# Main.net
KiCad netlist of a schematic drawn in Altium Designer
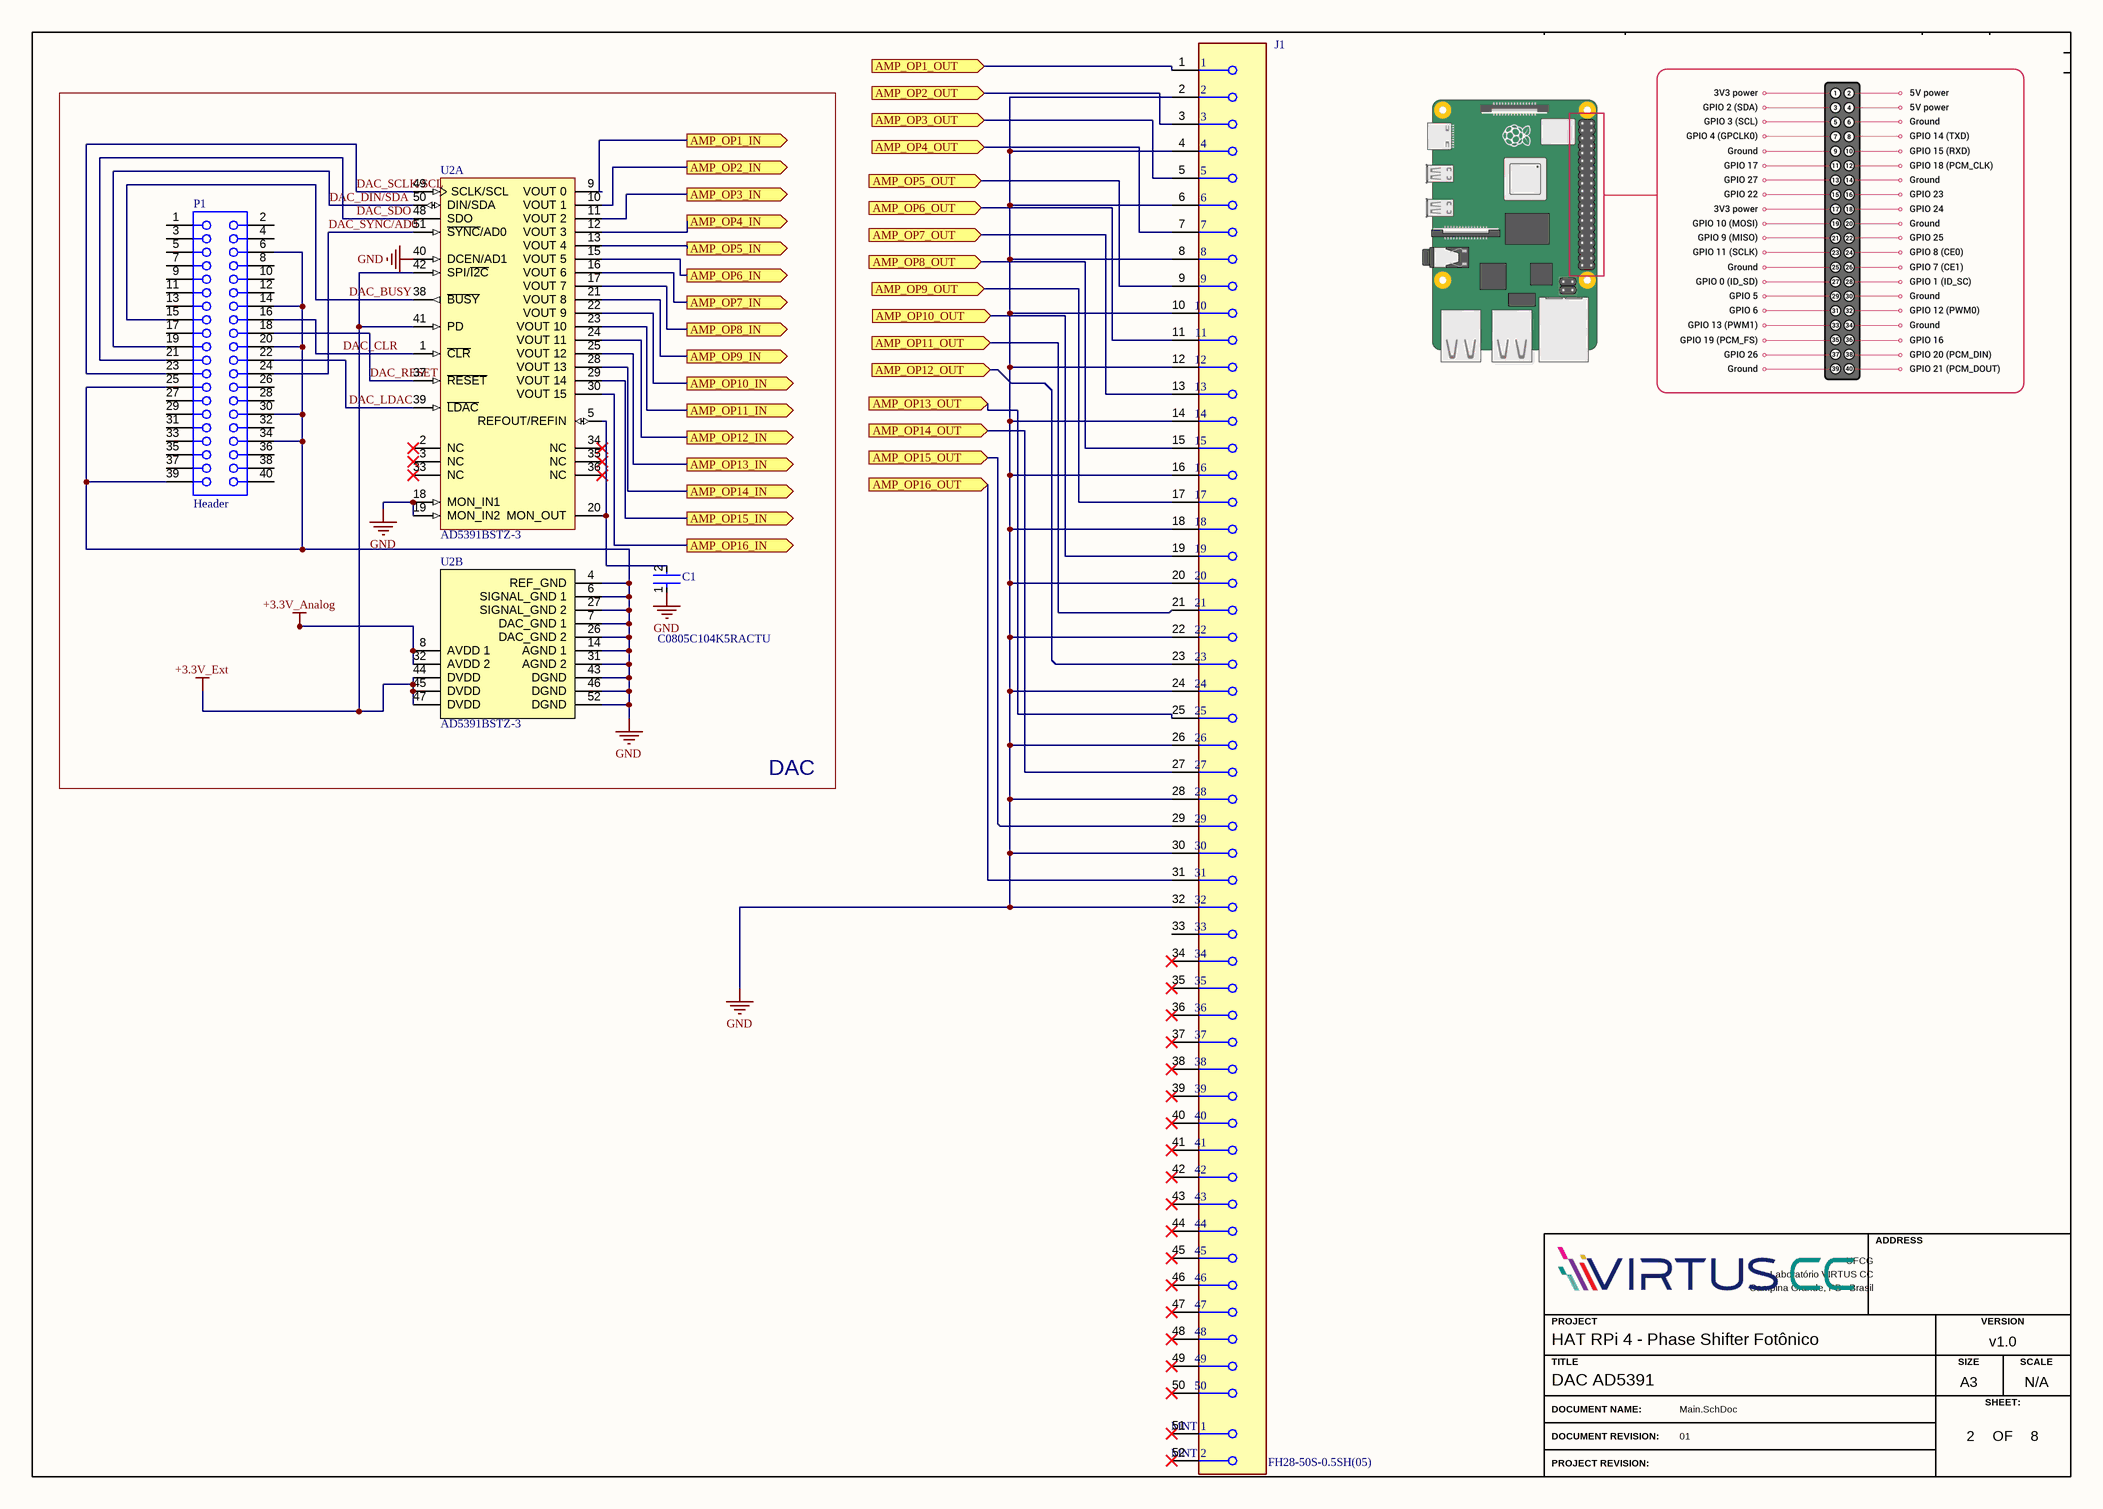
[diagram p0: Main.SchDoc]

(export (version "E")
  (design (tool "Eeschema 10.0.6"))
  (components
    (comp (ref "C1")
      (value "C0805C104K5RACTU")
      (footprint "FP-C0805C-DN-MFG")
      (description "CAP CER 0.1UF 50V X7R 0805")
      (fields
        (field (name "MANUFACTURER") "KEMET")
        (field (name "OCTOPART") "https://octopart.com/c0805c104k5ractu-kemet-143926")
      )
      (libsource (lib "Altium Content Vault") (part "b4654b650e69147ec39a6b967a45e02"))
    )
    (comp (ref "J1")
      (value "FH28-50S-0.5SH(05)")
      (footprint "FP-FH28-50S-0_5SH_05-MFG")
      (description "CONN FFC BOTTOM 50POS 0.50MM R/A")
      (fields
        (field (name "OCTOPART") "https://octopart.com/fh28-50s-0.5sh%2805%29-hirose-240232")
        (field (name "MANUFACTURER") "Hirose Electric Co Ltd")
      )
      (libsource (lib "Altium Content Vault") (part "b58b7e437d2d31add36c43a93be18f6"))
    )
    (comp (ref "P1")
      (value "Header")
      (footprint "61204021621")
      (description "THT Vertical Socket Header WR-PHD, Pitch 2.54 mm, Dual Row, 40 pins")
      (libsource (lib "Altium Content Vault") (part "Header_Female_2R_40P"))
    )
    (comp (ref "U2")
      (value "AD5391BSTZ-3")
      (footprint "ST-52_L")
      (fields (field (name "MANUFACTURER") "Analog Devices") (field (name "GENERIC PART NUMBER") "AD5391"))
      (libsource (lib "Altium Content Vault") (part "ADI-AD5391-ST-52"))
    )
  )
  (nets
    (net (code "1") (name "+3.3V_Analog") (class "Default")
      (node (ref "U2") (pin "32") (pinfunction "AVDD_2_32") (pintype "power_in"))
      (node (ref "U2") (pin "8") (pinfunction "AVDD_1_8") (pintype "power_in"))
    )
    (net (code "2") (name "+3.3V_Ext") (class "Default")
      (node (ref "U2") (pin "41") (pinfunction "PD_41") (pintype "input"))
      (node (ref "U2") (pin "42") (pinfunction "SPI/~{I2C}_42") (pintype "input"))
      (node (ref "U2") (pin "44") (pinfunction "DVDD_44") (pintype "power_in"))
      (node (ref "U2") (pin "45") (pinfunction "DVDD_45") (pintype "power_in"))
      (node (ref "U2") (pin "47") (pinfunction "DVDD_47") (pintype "power_in"))
    )
    (net (code "3") (name "/AMP_OP1_IN") (class "Default")
      (node (ref "U2") (pin "9") (pinfunction "VOUT_0_9") (pintype "tri_state"))
    )
    (net (code "4") (name "/AMP_OP1_OUT") (class "Default")
      (node (ref "J1") (pin "1") (pinfunction "1_1") (pintype "passive"))
    )
    (net (code "5") (name "/AMP_OP2_IN") (class "Default")
      (node (ref "U2") (pin "10") (pinfunction "VOUT_1_10") (pintype "tri_state"))
    )
    (net (code "6") (name "/AMP_OP2_OUT") (class "Default")
      (node (ref "J1") (pin "3") (pinfunction "3_3") (pintype "passive"))
    )
    (net (code "7") (name "/AMP_OP3_IN") (class "Default")
      (node (ref "U2") (pin "11") (pinfunction "VOUT_2_11") (pintype "tri_state"))
    )
    (net (code "8") (name "/AMP_OP3_OUT") (class "Default")
      (node (ref "J1") (pin "5") (pinfunction "5_5") (pintype "passive"))
    )
    (net (code "9") (name "/AMP_OP4_IN") (class "Default")
      (node (ref "U2") (pin "12") (pinfunction "VOUT_3_12") (pintype "tri_state"))
    )
    (net (code "10") (name "/AMP_OP4_OUT") (class "Default")
      (node (ref "J1") (pin "7") (pinfunction "7_7") (pintype "passive"))
    )
    (net (code "11") (name "/AMP_OP5_IN") (class "Default")
      (node (ref "U2") (pin "13") (pinfunction "VOUT_4_13") (pintype "tri_state"))
    )
    (net (code "12") (name "/AMP_OP5_OUT") (class "Default")
      (node (ref "J1") (pin "9") (pinfunction "9_9") (pintype "passive"))
    )
    (net (code "13") (name "/AMP_OP6_IN") (class "Default")
      (node (ref "U2") (pin "15") (pinfunction "VOUT_5_15") (pintype "tri_state"))
    )
    (net (code "14") (name "/AMP_OP6_OUT") (class "Default")
      (node (ref "J1") (pin "11") (pinfunction "11_11") (pintype "passive"))
    )
    (net (code "15") (name "/AMP_OP7_IN") (class "Default")
      (node (ref "U2") (pin "16") (pinfunction "VOUT_6_16") (pintype "tri_state"))
    )
    (net (code "16") (name "/AMP_OP7_OUT") (class "Default")
      (node (ref "J1") (pin "13") (pinfunction "13_13") (pintype "passive"))
    )
    (net (code "17") (name "/AMP_OP8_IN") (class "Default")
      (node (ref "U2") (pin "17") (pinfunction "VOUT_7_17") (pintype "tri_state"))
    )
    (net (code "18") (name "/AMP_OP8_OUT") (class "Default")
      (node (ref "J1") (pin "15") (pinfunction "15_15") (pintype "passive"))
    )
    (net (code "19") (name "/AMP_OP9_IN") (class "Default")
      (node (ref "U2") (pin "21") (pinfunction "VOUT_8_21") (pintype "tri_state"))
    )
    (net (code "20") (name "/AMP_OP9_OUT") (class "Default")
      (node (ref "J1") (pin "17") (pinfunction "17_17") (pintype "passive"))
    )
    (net (code "21") (name "/AMP_OP10_IN") (class "Default")
      (node (ref "U2") (pin "22") (pinfunction "VOUT_9_22") (pintype "tri_state"))
    )
    (net (code "22") (name "/AMP_OP10_OUT") (class "Default")
      (node (ref "J1") (pin "19") (pinfunction "19_19") (pintype "passive"))
    )
    (net (code "23") (name "/AMP_OP11_IN") (class "Default")
      (node (ref "U2") (pin "23") (pinfunction "VOUT_10_23") (pintype "tri_state"))
    )
    (net (code "24") (name "/AMP_OP11_OUT") (class "Default")
      (node (ref "J1") (pin "21") (pinfunction "21_21") (pintype "passive"))
    )
    (net (code "25") (name "/AMP_OP12_IN") (class "Default")
      (node (ref "U2") (pin "24") (pinfunction "VOUT_11_24") (pintype "tri_state"))
    )
    (net (code "26") (name "/AMP_OP12_OUT") (class "Default")
      (node (ref "J1") (pin "23") (pinfunction "23_23") (pintype "passive"))
    )
    (net (code "27") (name "/AMP_OP13_IN") (class "Default")
      (node (ref "U2") (pin "25") (pinfunction "VOUT_12_25") (pintype "tri_state"))
    )
    (net (code "28") (name "/AMP_OP13_OUT") (class "Default")
      (node (ref "J1") (pin "25") (pinfunction "25_25") (pintype "passive"))
    )
    (net (code "29") (name "/AMP_OP14_IN") (class "Default")
      (node (ref "U2") (pin "28") (pinfunction "VOUT_13_28") (pintype "tri_state"))
    )
    (net (code "30") (name "/AMP_OP14_OUT") (class "Default")
      (node (ref "J1") (pin "27") (pinfunction "27_27") (pintype "passive"))
    )
    (net (code "31") (name "/AMP_OP15_IN") (class "Default")
      (node (ref "U2") (pin "29") (pinfunction "VOUT_14_29") (pintype "tri_state"))
    )
    (net (code "32") (name "/AMP_OP15_OUT") (class "Default")
      (node (ref "J1") (pin "29") (pinfunction "29_29") (pintype "passive"))
    )
    (net (code "33") (name "/AMP_OP16_IN") (class "Default")
      (node (ref "U2") (pin "30") (pinfunction "VOUT_15_30") (pintype "tri_state"))
    )
    (net (code "34") (name "/AMP_OP16_OUT") (class "Default")
      (node (ref "J1") (pin "31") (pinfunction "31_31") (pintype "passive"))
    )
    (net (code "35") (name "/DAC_BUSY") (class "Default")
      (node (ref "P1") (pin "15") (pinfunction "15_15") (pintype "passive"))
      (node (ref "U2") (pin "38") (pinfunction "~{BUSY}_38") (pintype "output"))
    )
    (net (code "36") (name "/DAC_CLR") (class "Default")
      (node (ref "P1") (pin "16") (pinfunction "16_16") (pintype "passive"))
      (node (ref "U2") (pin "1") (pinfunction "~{CLR}_1") (pintype "input"))
    )
    (net (code "37") (name "/DAC_DIN{slash}SDA") (class "Default")
      (node (ref "P1") (pin "19") (pinfunction "19_19") (pintype "passive"))
      (node (ref "U2") (pin "50") (pinfunction "DIN/SDA_50") (pintype "bidirectional"))
    )
    (net (code "38") (name "/DAC_LDAC") (class "Default")
      (node (ref "P1") (pin "22") (pinfunction "22_22") (pintype "passive"))
      (node (ref "U2") (pin "39") (pinfunction "~{LDAC}_39") (pintype "input"))
    )
    (net (code "39") (name "/DAC_RESET") (class "Default")
      (node (ref "P1") (pin "18") (pinfunction "18_18") (pintype "passive"))
      (node (ref "U2") (pin "37") (pinfunction "~{RESET}_37") (pintype "input"))
    )
    (net (code "40") (name "/DAC_SCLK{slash}SCL") (class "Default")
      (node (ref "P1") (pin "23") (pinfunction "23_23") (pintype "passive"))
      (node (ref "U2") (pin "49") (pinfunction "SCLK/SCL_49") (pintype "input"))
    )
    (net (code "41") (name "/DAC_SDO") (class "Default")
      (node (ref "P1") (pin "21") (pinfunction "21_21") (pintype "passive"))
      (node (ref "U2") (pin "48") (pinfunction "SDO_48") (pintype "tri_state"))
    )
    (net (code "42") (name "/DAC_SYNC{slash}AD0") (class "Default")
      (node (ref "P1") (pin "24") (pinfunction "24_24") (pintype "passive"))
      (node (ref "U2") (pin "51") (pinfunction "~{SYNC}/AD0_51") (pintype "input"))
    )
    (net (code "43") (name "GND") (class "Default")
      (node (ref "C1") (pin "1") (pinfunction "1_1") (pintype "passive"))
      (node (ref "J1") (pin "10") (pinfunction "10_10") (pintype "passive"))
      (node (ref "J1") (pin "12") (pinfunction "12_12") (pintype "passive"))
      (node (ref "J1") (pin "14") (pinfunction "14_14") (pintype "passive"))
      (node (ref "J1") (pin "16") (pinfunction "16_16") (pintype "passive"))
      (node (ref "J1") (pin "18") (pinfunction "18_18") (pintype "passive"))
      (node (ref "J1") (pin "2") (pinfunction "2_2") (pintype "passive"))
      (node (ref "J1") (pin "20") (pinfunction "20_20") (pintype "passive"))
      (node (ref "J1") (pin "22") (pinfunction "22_22") (pintype "passive"))
      (node (ref "J1") (pin "24") (pinfunction "24_24") (pintype "passive"))
      (node (ref "J1") (pin "26") (pinfunction "26_26") (pintype "passive"))
      (node (ref "J1") (pin "28") (pinfunction "28_28") (pintype "passive"))
      (node (ref "J1") (pin "30") (pinfunction "30_30") (pintype "passive"))
      (node (ref "J1") (pin "32") (pinfunction "32_32") (pintype "passive"))
      (node (ref "J1") (pin "4") (pinfunction "4_4") (pintype "passive"))
      (node (ref "J1") (pin "6") (pinfunction "6_6") (pintype "passive"))
      (node (ref "J1") (pin "8") (pinfunction "8_8") (pintype "passive"))
      (node (ref "P1") (pin "14") (pinfunction "14_14") (pintype "passive"))
      (node (ref "P1") (pin "20") (pinfunction "20_20") (pintype "passive"))
      (node (ref "P1") (pin "25") (pinfunction "25_25") (pintype "passive"))
      (node (ref "P1") (pin "30") (pinfunction "30_30") (pintype "passive"))
      (node (ref "P1") (pin "34") (pinfunction "34_34") (pintype "passive"))
      (node (ref "P1") (pin "39") (pinfunction "39_39") (pintype "passive"))
      (node (ref "P1") (pin "6") (pinfunction "6_6") (pintype "passive"))
      (node (ref "U2") (pin "14") (pinfunction "AGND_1_14") (pintype "power_in"))
      (node (ref "U2") (pin "18") (pinfunction "MON_IN1_18") (pintype "input"))
      (node (ref "U2") (pin "19") (pinfunction "MON_IN2_19") (pintype "input"))
      (node (ref "U2") (pin "26") (pinfunction "DAC_GND_2_26") (pintype "power_in"))
      (node (ref "U2") (pin "27") (pinfunction "SIGNAL_GND_2_27") (pintype "power_in"))
      (node (ref "U2") (pin "31") (pinfunction "AGND_2_31") (pintype "power_in"))
      (node (ref "U2") (pin "4") (pinfunction "REF_GND_4") (pintype "power_in"))
      (node (ref "U2") (pin "40") (pinfunction "DCEN/AD1_40") (pintype "input"))
      (node (ref "U2") (pin "43") (pinfunction "DGND_43") (pintype "power_in"))
      (node (ref "U2") (pin "46") (pinfunction "DGND_46") (pintype "power_in"))
      (node (ref "U2") (pin "52") (pinfunction "DGND_52") (pintype "power_in"))
      (node (ref "U2") (pin "6") (pinfunction "SIGNAL_GND_1_6") (pintype "power_in"))
      (node (ref "U2") (pin "7") (pinfunction "DAC_GND_1_7") (pintype "power_in"))
    )
    (net (code "44") (name "Net-(U2A-MON_OUT)") (class "Default")
      (node (ref "C1") (pin "2") (pinfunction "2_2") (pintype "passive"))
      (node (ref "U2") (pin "20") (pinfunction "MON_OUT_20") (pintype "tri_state"))
      (node (ref "U2") (pin "5") (pinfunction "REFOUT/REFIN_5") (pintype "bidirectional"))
    )
    (net (code "45") (name "unconnected-(J1-MNT_1-Pad51)") (class "Default")
      (node (ref "J1") (pin "51") (pinfunction "MNT_1_51") (pintype "passive+no_connect"))
    )
    (net (code "46") (name "unconnected-(J1-MNT_2-Pad52)") (class "Default")
      (node (ref "J1") (pin "52") (pinfunction "MNT_2_52") (pintype "passive+no_connect"))
    )
    (net (code "47") (name "unconnected-(J1-Pad33)") (class "Default")
      (node (ref "J1") (pin "33") (pinfunction "33_33") (pintype "passive"))
    )
    (net (code "48") (name "unconnected-(J1-Pad34)") (class "Default")
      (node (ref "J1") (pin "34") (pinfunction "34_34") (pintype "passive+no_connect"))
    )
    (net (code "49") (name "unconnected-(J1-Pad35)") (class "Default")
      (node (ref "J1") (pin "35") (pinfunction "35_35") (pintype "passive+no_connect"))
    )
    (net (code "50") (name "unconnected-(J1-Pad36)") (class "Default")
      (node (ref "J1") (pin "36") (pinfunction "36_36") (pintype "passive+no_connect"))
    )
    (net (code "51") (name "unconnected-(J1-Pad37)") (class "Default")
      (node (ref "J1") (pin "37") (pinfunction "37_37") (pintype "passive+no_connect"))
    )
    (net (code "52") (name "unconnected-(J1-Pad38)") (class "Default")
      (node (ref "J1") (pin "38") (pinfunction "38_38") (pintype "passive+no_connect"))
    )
    (net (code "53") (name "unconnected-(J1-Pad39)") (class "Default")
      (node (ref "J1") (pin "39") (pinfunction "39_39") (pintype "passive+no_connect"))
    )
    (net (code "54") (name "unconnected-(J1-Pad40)") (class "Default")
      (node (ref "J1") (pin "40") (pinfunction "40_40") (pintype "passive+no_connect"))
    )
    (net (code "55") (name "unconnected-(J1-Pad41)") (class "Default")
      (node (ref "J1") (pin "41") (pinfunction "41_41") (pintype "passive+no_connect"))
    )
    (net (code "56") (name "unconnected-(J1-Pad42)") (class "Default")
      (node (ref "J1") (pin "42") (pinfunction "42_42") (pintype "passive+no_connect"))
    )
    (net (code "57") (name "unconnected-(J1-Pad43)") (class "Default")
      (node (ref "J1") (pin "43") (pinfunction "43_43") (pintype "passive+no_connect"))
    )
    (net (code "58") (name "unconnected-(J1-Pad44)") (class "Default")
      (node (ref "J1") (pin "44") (pinfunction "44_44") (pintype "passive+no_connect"))
    )
    (net (code "59") (name "unconnected-(J1-Pad45)") (class "Default")
      (node (ref "J1") (pin "45") (pinfunction "45_45") (pintype "passive+no_connect"))
    )
    (net (code "60") (name "unconnected-(J1-Pad46)") (class "Default")
      (node (ref "J1") (pin "46") (pinfunction "46_46") (pintype "passive+no_connect"))
    )
    (net (code "61") (name "unconnected-(J1-Pad47)") (class "Default")
      (node (ref "J1") (pin "47") (pinfunction "47_47") (pintype "passive+no_connect"))
    )
    (net (code "62") (name "unconnected-(J1-Pad48)") (class "Default")
      (node (ref "J1") (pin "48") (pinfunction "48_48") (pintype "passive+no_connect"))
    )
    (net (code "63") (name "unconnected-(J1-Pad49)") (class "Default")
      (node (ref "J1") (pin "49") (pinfunction "49_49") (pintype "passive+no_connect"))
    )
    (net (code "64") (name "unconnected-(J1-Pad50)") (class "Default")
      (node (ref "J1") (pin "50") (pinfunction "50_50") (pintype "passive+no_connect"))
    )
    (net (code "65") (name "unconnected-(P1-Pad1)") (class "Default")
      (node (ref "P1") (pin "1") (pinfunction "1_1") (pintype "passive"))
    )
    (net (code "66") (name "unconnected-(P1-Pad2)") (class "Default")
      (node (ref "P1") (pin "2") (pinfunction "2_2") (pintype "passive"))
    )
    (net (code "67") (name "unconnected-(P1-Pad3)") (class "Default")
      (node (ref "P1") (pin "3") (pinfunction "3_3") (pintype "passive"))
    )
    (net (code "68") (name "unconnected-(P1-Pad4)") (class "Default")
      (node (ref "P1") (pin "4") (pinfunction "4_4") (pintype "passive"))
    )
    (net (code "69") (name "unconnected-(P1-Pad5)") (class "Default")
      (node (ref "P1") (pin "5") (pinfunction "5_5") (pintype "passive"))
    )
    (net (code "70") (name "unconnected-(P1-Pad7)") (class "Default")
      (node (ref "P1") (pin "7") (pinfunction "7_7") (pintype "passive"))
    )
    (net (code "71") (name "unconnected-(P1-Pad8)") (class "Default")
      (node (ref "P1") (pin "8") (pinfunction "8_8") (pintype "passive"))
    )
    (net (code "72") (name "unconnected-(P1-Pad9)") (class "Default")
      (node (ref "P1") (pin "9") (pinfunction "9_9") (pintype "passive"))
    )
    (net (code "73") (name "unconnected-(P1-Pad10)") (class "Default")
      (node (ref "P1") (pin "10") (pinfunction "10_10") (pintype "passive"))
    )
    (net (code "74") (name "unconnected-(P1-Pad11)") (class "Default")
      (node (ref "P1") (pin "11") (pinfunction "11_11") (pintype "passive"))
    )
    (net (code "75") (name "unconnected-(P1-Pad12)") (class "Default")
      (node (ref "P1") (pin "12") (pinfunction "12_12") (pintype "passive"))
    )
    (net (code "76") (name "unconnected-(P1-Pad13)") (class "Default")
      (node (ref "P1") (pin "13") (pinfunction "13_13") (pintype "passive"))
    )
    (net (code "77") (name "unconnected-(P1-Pad17)") (class "Default")
      (node (ref "P1") (pin "17") (pinfunction "17_17") (pintype "passive"))
    )
    (net (code "78") (name "unconnected-(P1-Pad26)") (class "Default")
      (node (ref "P1") (pin "26") (pinfunction "26_26") (pintype "passive"))
    )
    (net (code "79") (name "unconnected-(P1-Pad27)") (class "Default")
      (node (ref "P1") (pin "27") (pinfunction "27_27") (pintype "passive"))
    )
    (net (code "80") (name "unconnected-(P1-Pad28)") (class "Default")
      (node (ref "P1") (pin "28") (pinfunction "28_28") (pintype "passive"))
    )
    (net (code "81") (name "unconnected-(P1-Pad29)") (class "Default")
      (node (ref "P1") (pin "29") (pinfunction "29_29") (pintype "passive"))
    )
    (net (code "82") (name "unconnected-(P1-Pad31)") (class "Default")
      (node (ref "P1") (pin "31") (pinfunction "31_31") (pintype "passive"))
    )
    (net (code "83") (name "unconnected-(P1-Pad32)") (class "Default")
      (node (ref "P1") (pin "32") (pinfunction "32_32") (pintype "passive"))
    )
    (net (code "84") (name "unconnected-(P1-Pad33)") (class "Default")
      (node (ref "P1") (pin "33") (pinfunction "33_33") (pintype "passive"))
    )
    (net (code "85") (name "unconnected-(P1-Pad35)") (class "Default")
      (node (ref "P1") (pin "35") (pinfunction "35_35") (pintype "passive"))
    )
    (net (code "86") (name "unconnected-(P1-Pad36)") (class "Default")
      (node (ref "P1") (pin "36") (pinfunction "36_36") (pintype "passive"))
    )
    (net (code "87") (name "unconnected-(P1-Pad37)") (class "Default")
      (node (ref "P1") (pin "37") (pinfunction "37_37") (pintype "passive"))
    )
    (net (code "88") (name "unconnected-(P1-Pad38)") (class "Default")
      (node (ref "P1") (pin "38") (pinfunction "38_38") (pintype "passive"))
    )
    (net (code "89") (name "unconnected-(P1-Pad40)") (class "Default")
      (node (ref "P1") (pin "40") (pinfunction "40_40") (pintype "passive"))
    )
    (net (code "90") (name "unconnected-(U2A-NC-Pad2)") (class "Default")
      (node (ref "U2") (pin "2") (pinfunction "NC_2") (pintype "passive+no_connect"))
    )
    (net (code "91") (name "unconnected-(U2A-NC-Pad3)") (class "Default")
      (node (ref "U2") (pin "3") (pinfunction "NC_3") (pintype "passive+no_connect"))
    )
    (net (code "92") (name "unconnected-(U2A-NC-Pad33)") (class "Default")
      (node (ref "U2") (pin "33") (pinfunction "NC_33") (pintype "passive+no_connect"))
    )
    (net (code "93") (name "unconnected-(U2A-NC-Pad34)") (class "Default")
      (node (ref "U2") (pin "34") (pinfunction "NC_34") (pintype "passive+no_connect"))
    )
    (net (code "94") (name "unconnected-(U2A-NC-Pad35)") (class "Default")
      (node (ref "U2") (pin "35") (pinfunction "NC_35") (pintype "passive+no_connect"))
    )
    (net (code "95") (name "unconnected-(U2A-NC-Pad36)") (class "Default")
      (node (ref "U2") (pin "36") (pinfunction "NC_36") (pintype "passive+no_connect"))
    )
  )
)
